# ProProject_NFC_SJTU-_-NFC.net
KiCad netlist of a schematic drawn in EasyEDA Pro
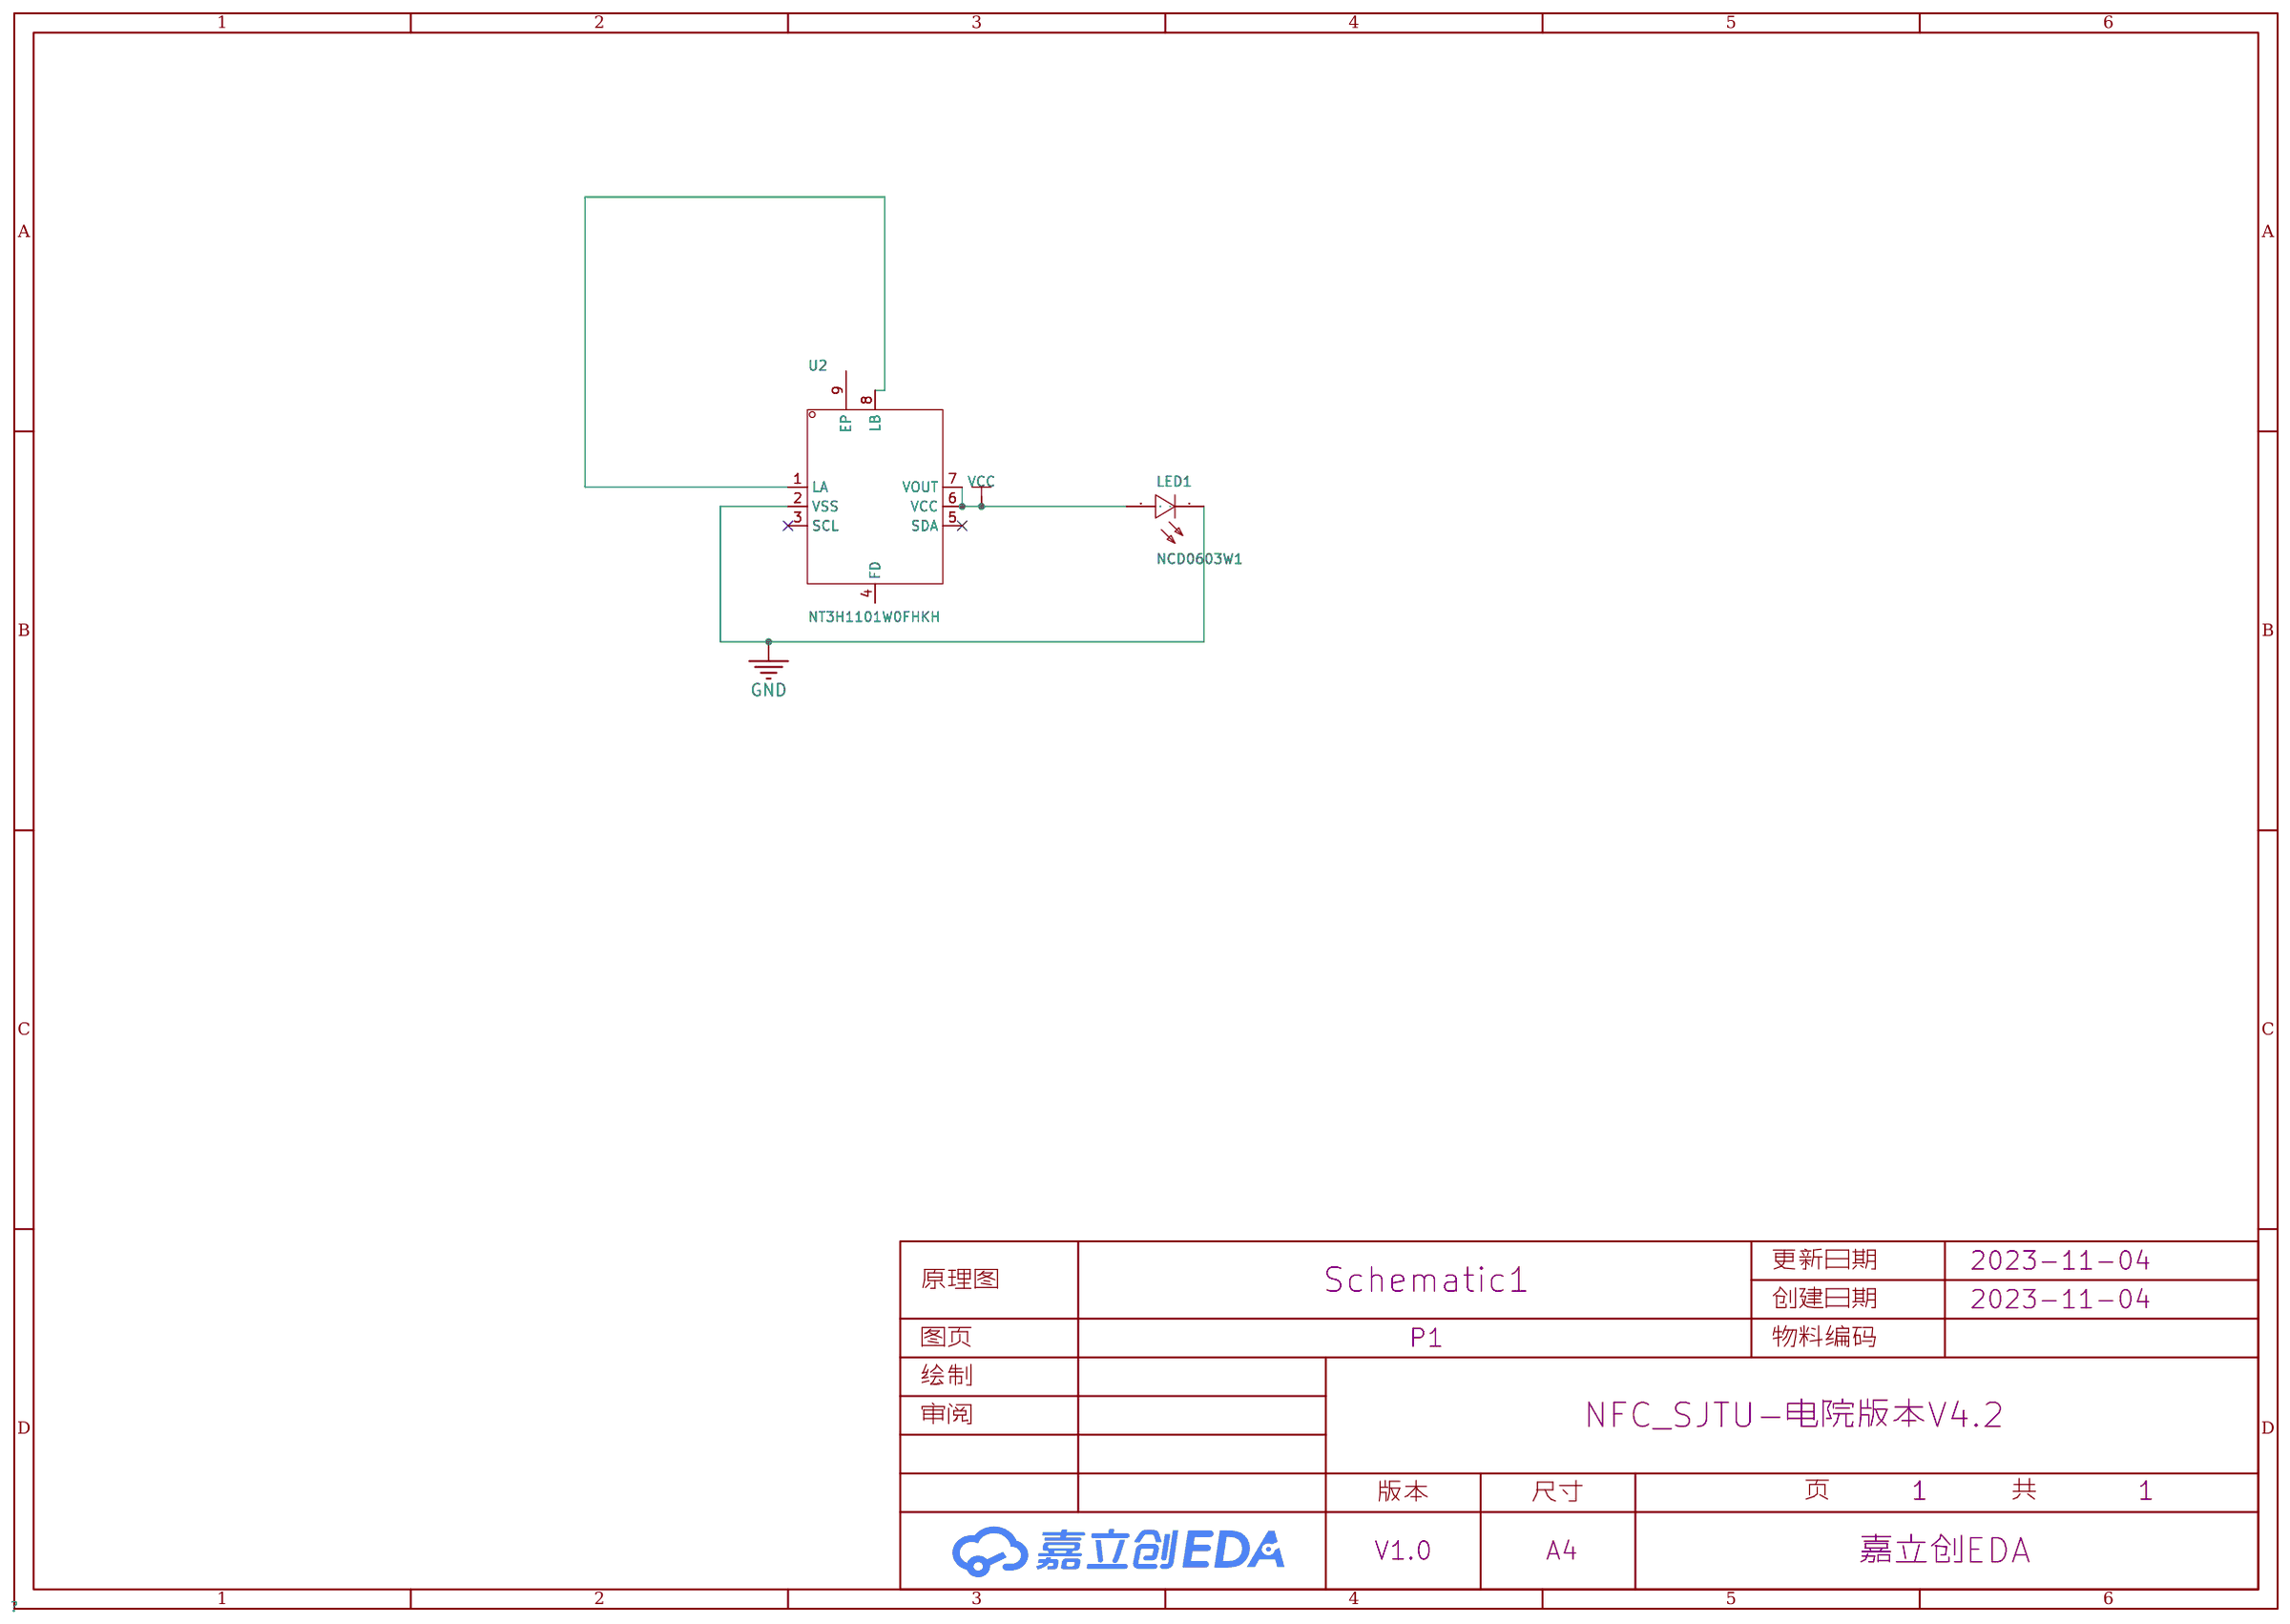
[diagram p0: schematic sheet]

(export (version "E")
  (design (tool "Eeschema 10.0.6"))
  (components
    (comp (ref "LED1")
      (value "NCD0603W1")
      (footprint "easyedapro:LED0603-RD")
      (description "发光颜色:白灯;")
      (fields (field (name "Manufacturer") "国星光电"))
      (libsource (lib "easyedapro") (part "FC-D1608WD-460H5"))
    )
    (comp (ref "U2")
      (value "NT3H1101W0FHKH")
      (footprint "easyedapro:XQFN-8_L1.6-W1.6-P0.50-BR")
      (fields (field (name "Manufacturer") "NXP(恩智浦)"))
      (libsource (lib "easyedapro") (part "NT3H1101W0FHKH"))
    )
  )
  (nets
    (net (code "1") (name "GND") (class "Default")
      (node (ref "LED1") (pin "1") (pinfunction "-_1") (pintype "input"))
      (node (ref "U2") (pin "2") (pinfunction "VSS_2") (pintype "input"))
    )
    (net (code "2") (name "Net-(U2-LA)") (class "Default")
      (node (ref "U2") (pin "1") (pinfunction "LA_1") (pintype "input"))
      (node (ref "U2") (pin "8") (pinfunction "LB_8") (pintype "input"))
    )
    (net (code "3") (name "VCC") (class "Default")
      (node (ref "LED1") (pin "2") (pinfunction "+_2") (pintype "input"))
      (node (ref "U2") (pin "6") (pinfunction "VCC_6") (pintype "input"))
      (node (ref "U2") (pin "7") (pinfunction "VOUT_7") (pintype "input"))
    )
    (net (code "4") (name "unconnected-(U2-EP-Pad9)") (class "Default")
      (node (ref "U2") (pin "9") (pinfunction "EP_9") (pintype "input"))
    )
    (net (code "5") (name "unconnected-(U2-FD-Pad4)") (class "Default")
      (node (ref "U2") (pin "4") (pinfunction "FD_4") (pintype "input"))
    )
    (net (code "6") (name "unconnected-(U2-SCL-Pad3)") (class "Default")
      (node (ref "U2") (pin "3") (pinfunction "SCL_3") (pintype "input+no_connect"))
    )
    (net (code "7") (name "unconnected-(U2-SDA-Pad5)") (class "Default")
      (node (ref "U2") (pin "5") (pinfunction "SDA_5") (pintype "input+no_connect"))
    )
  )
)
